# LEDs.net
KiCad netlist of a schematic drawn in Altium Designer
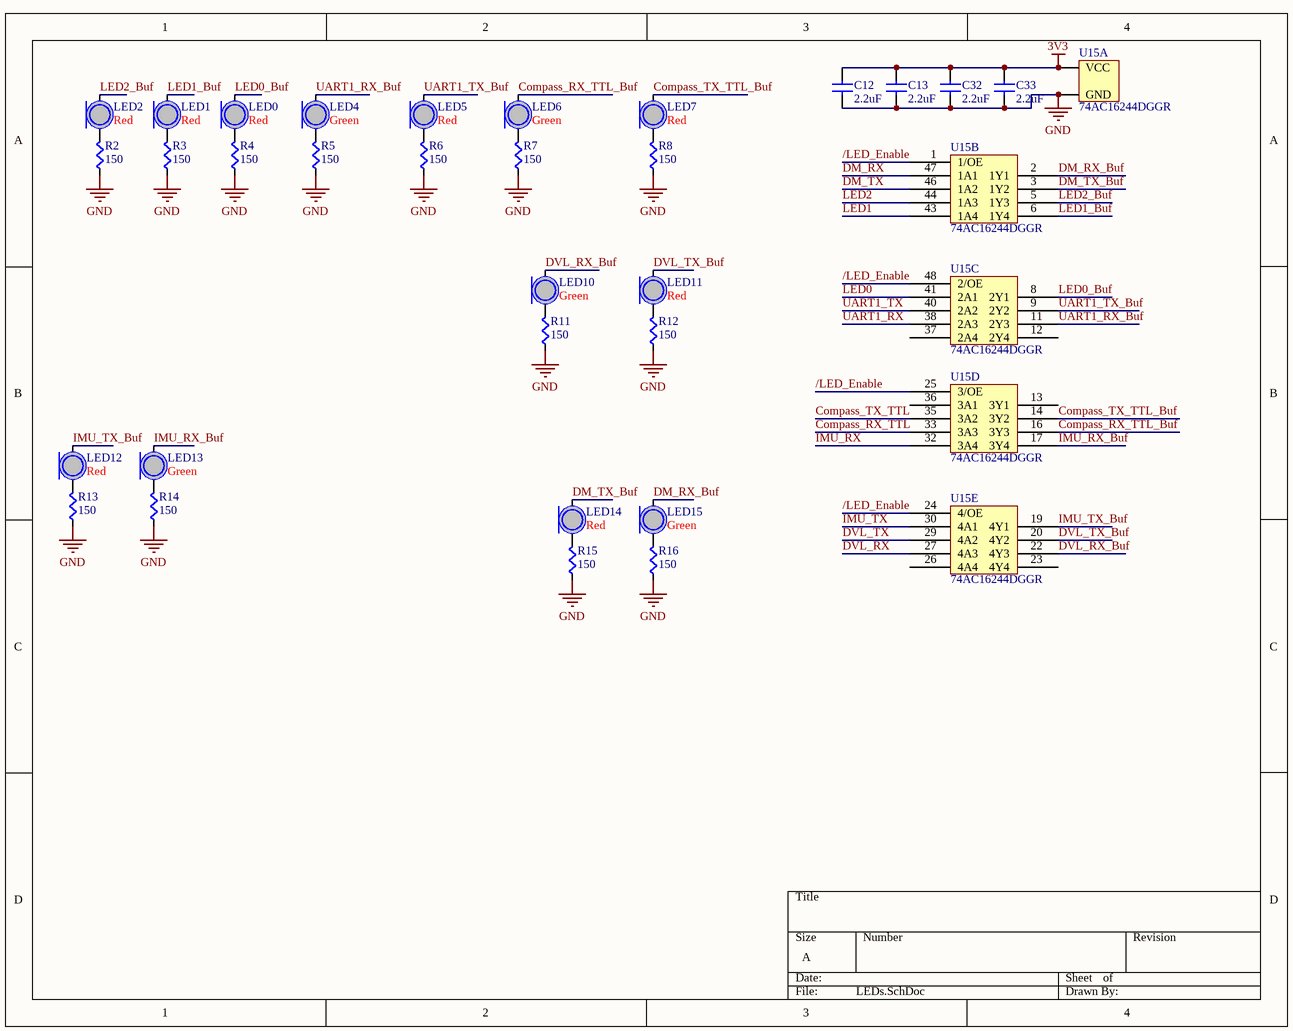
[diagram p0: LEDs.SchDoc]

(export (version "E")
  (design (tool "Eeschema 10.0.6"))
  (components
    (comp (ref "C12")
      (value "2.2uF")
      (footprint "CAPC0603")
      (fields (field (name "Comment") "Cap"))
      (libsource (lib "SubjuGator8") (part "Cap"))
    )
    (comp (ref "C13")
      (value "2.2uF")
      (footprint "CAPC0603")
      (fields (field (name "Comment") "Cap"))
      (libsource (lib "SubjuGator8") (part "Cap"))
    )
    (comp (ref "C32")
      (value "2.2uF")
      (footprint "CAPC0603")
      (fields (field (name "Comment") "Cap"))
      (libsource (lib "SubjuGator8") (part "Cap"))
    )
    (comp (ref "C33")
      (value "2.2uF")
      (footprint "CAPC0603")
      (fields (field (name "Comment") "Cap"))
      (libsource (lib "SubjuGator8") (part "Cap"))
    )
    (comp (ref "LED0")
      (value "LED")
      (footprint "LED0603")
      (fields (field (name "COLOR") "Red"))
      (libsource (lib "SubjuGator8") (part "LED"))
    )
    (comp (ref "LED1")
      (value "LED")
      (footprint "LED0603")
      (fields (field (name "COLOR") "Red"))
      (libsource (lib "SubjuGator8") (part "LED"))
    )
    (comp (ref "LED2")
      (value "LED")
      (footprint "LED0603")
      (fields (field (name "COLOR") "Red"))
      (libsource (lib "SubjuGator8") (part "LED"))
    )
    (comp (ref "LED4")
      (value "LED")
      (footprint "LED0603")
      (fields (field (name "COLOR") "Green"))
      (libsource (lib "SubjuGator8") (part "LED"))
    )
    (comp (ref "LED5")
      (value "LED")
      (footprint "LED0603")
      (fields (field (name "COLOR") "Red"))
      (libsource (lib "SubjuGator8") (part "LED"))
    )
    (comp (ref "LED6")
      (value "LED")
      (footprint "LED0603")
      (fields (field (name "COLOR") "Green"))
      (libsource (lib "SubjuGator8") (part "LED"))
    )
    (comp (ref "LED7")
      (value "LED")
      (footprint "LED0603")
      (fields (field (name "COLOR") "Red"))
      (libsource (lib "SubjuGator8") (part "LED"))
    )
    (comp (ref "LED10")
      (value "LED")
      (footprint "LED0603")
      (fields (field (name "COLOR") "Green"))
      (libsource (lib "SubjuGator8") (part "LED"))
    )
    (comp (ref "LED11")
      (value "LED")
      (footprint "LED0603")
      (fields (field (name "COLOR") "Red"))
      (libsource (lib "SubjuGator8") (part "LED"))
    )
    (comp (ref "LED12")
      (value "LED")
      (footprint "LED0603")
      (fields (field (name "COLOR") "Red"))
      (libsource (lib "SubjuGator8") (part "LED"))
    )
    (comp (ref "LED13")
      (value "LED")
      (footprint "LED0603")
      (fields (field (name "COLOR") "Green"))
      (libsource (lib "SubjuGator8") (part "LED"))
    )
    (comp (ref "LED14")
      (value "LED")
      (footprint "LED0603")
      (fields (field (name "COLOR") "Red"))
      (libsource (lib "SubjuGator8") (part "LED"))
    )
    (comp (ref "LED15")
      (value "LED")
      (footprint "LED0603")
      (fields (field (name "COLOR") "Green"))
      (libsource (lib "SubjuGator8") (part "LED"))
    )
    (comp (ref "R2")
      (value "150")
      (footprint "RES0603")
      (fields (field (name "Comment") "Res"))
      (libsource (lib "SubjuGator8") (part "Res"))
    )
    (comp (ref "R3")
      (value "150")
      (footprint "RES0603")
      (fields (field (name "Comment") "Res"))
      (libsource (lib "SubjuGator8") (part "Res"))
    )
    (comp (ref "R4")
      (value "150")
      (footprint "RES0603")
      (fields (field (name "Comment") "Res"))
      (libsource (lib "SubjuGator8") (part "Res"))
    )
    (comp (ref "R5")
      (value "150")
      (footprint "RES0603")
      (fields (field (name "Comment") "Res"))
      (libsource (lib "SubjuGator8") (part "Res"))
    )
    (comp (ref "R6")
      (value "150")
      (footprint "RES0603")
      (fields (field (name "Comment") "Res"))
      (libsource (lib "SubjuGator8") (part "Res"))
    )
    (comp (ref "R7")
      (value "150")
      (footprint "RES0603")
      (fields (field (name "Comment") "Res"))
      (libsource (lib "SubjuGator8") (part "Res"))
    )
    (comp (ref "R8")
      (value "150")
      (footprint "RES0603")
      (fields (field (name "Comment") "Res"))
      (libsource (lib "SubjuGator8") (part "Res"))
    )
    (comp (ref "R11")
      (value "150")
      (footprint "RES0603")
      (fields (field (name "Comment") "Res"))
      (libsource (lib "SubjuGator8") (part "Res"))
    )
    (comp (ref "R12")
      (value "150")
      (footprint "RES0603")
      (fields (field (name "Comment") "Res"))
      (libsource (lib "SubjuGator8") (part "Res"))
    )
    (comp (ref "R13")
      (value "150")
      (footprint "RES0603")
      (fields (field (name "Comment") "Res"))
      (libsource (lib "SubjuGator8") (part "Res"))
    )
    (comp (ref "R14")
      (value "150")
      (footprint "RES0603")
      (fields (field (name "Comment") "Res"))
      (libsource (lib "SubjuGator8") (part "Res"))
    )
    (comp (ref "R15")
      (value "150")
      (footprint "RES0603")
      (fields (field (name "Comment") "Res"))
      (libsource (lib "SubjuGator8") (part "Res"))
    )
    (comp (ref "R16")
      (value "150")
      (footprint "RES0603")
      (fields (field (name "Comment") "Res"))
      (libsource (lib "SubjuGator8") (part "Res"))
    )
    (comp (ref "U15")
      (value "74AC16244DGGR")
      (footprint "74AC16244DGGR")
      (description "IC BUFF/DVR TRI-ST 16BIT 48TSSOP")
      (libsource (lib "SubjuGator8") (part "74AC16244DGGR"))
    )
  )
  (nets
    (net (code "1") (name "/Compass_RX_TTL") (class "Default")
      (node (ref "U15") (pin "33") (pinfunction "3A3_33") (pintype "passive"))
    )
    (net (code "2") (name "/Compass_RX_TTL_Buf") (class "Default")
      (node (ref "LED6") (pin "A") (pinfunction "A_A") (pintype "passive"))
      (node (ref "U15") (pin "16") (pinfunction "3Y3_16") (pintype "passive"))
    )
    (net (code "3") (name "/Compass_TX_TTL") (class "Default")
      (node (ref "U15") (pin "35") (pinfunction "3A2_35") (pintype "passive"))
    )
    (net (code "4") (name "/Compass_TX_TTL_Buf") (class "Default")
      (node (ref "LED7") (pin "A") (pinfunction "A_A") (pintype "passive"))
      (node (ref "U15") (pin "14") (pinfunction "3Y2_14") (pintype "passive"))
    )
    (net (code "5") (name "/DM_RX") (class "Default")
      (node (ref "U15") (pin "47") (pinfunction "1A1_47") (pintype "passive"))
    )
    (net (code "6") (name "/DM_RX_Buf") (class "Default")
      (node (ref "LED15") (pin "A") (pinfunction "A_A") (pintype "passive"))
      (node (ref "U15") (pin "2") (pinfunction "1Y1_2") (pintype "passive"))
    )
    (net (code "7") (name "/DM_TX") (class "Default")
      (node (ref "U15") (pin "46") (pinfunction "1A2_46") (pintype "passive"))
    )
    (net (code "8") (name "/DM_TX_Buf") (class "Default")
      (node (ref "LED14") (pin "A") (pinfunction "A_A") (pintype "passive"))
      (node (ref "U15") (pin "3") (pinfunction "1Y2_3") (pintype "passive"))
    )
    (net (code "9") (name "/DVL_RX") (class "Default")
      (node (ref "U15") (pin "27") (pinfunction "4A3_27") (pintype "passive"))
    )
    (net (code "10") (name "/DVL_RX_Buf") (class "Default")
      (node (ref "LED10") (pin "A") (pinfunction "A_A") (pintype "passive"))
      (node (ref "U15") (pin "22") (pinfunction "4Y3_22") (pintype "passive"))
    )
    (net (code "11") (name "/DVL_TX") (class "Default")
      (node (ref "U15") (pin "29") (pinfunction "4A2_29") (pintype "passive"))
    )
    (net (code "12") (name "/DVL_TX_Buf") (class "Default")
      (node (ref "LED11") (pin "A") (pinfunction "A_A") (pintype "passive"))
      (node (ref "U15") (pin "20") (pinfunction "4Y2_20") (pintype "passive"))
    )
    (net (code "13") (name "/IMU_RX") (class "Default")
      (node (ref "U15") (pin "32") (pinfunction "3A4_32") (pintype "passive"))
    )
    (net (code "14") (name "/IMU_RX_Buf") (class "Default")
      (node (ref "LED13") (pin "A") (pinfunction "A_A") (pintype "passive"))
      (node (ref "U15") (pin "17") (pinfunction "3Y4_17") (pintype "passive"))
    )
    (net (code "15") (name "/IMU_TX") (class "Default")
      (node (ref "U15") (pin "30") (pinfunction "4A1_30") (pintype "passive"))
    )
    (net (code "16") (name "/IMU_TX_Buf") (class "Default")
      (node (ref "LED12") (pin "A") (pinfunction "A_A") (pintype "passive"))
      (node (ref "U15") (pin "19") (pinfunction "4Y1_19") (pintype "passive"))
    )
    (net (code "17") (name "/LED0") (class "Default")
      (node (ref "U15") (pin "41") (pinfunction "2A1_41") (pintype "passive"))
    )
    (net (code "18") (name "/LED0_Buf") (class "Default")
      (node (ref "LED0") (pin "A") (pinfunction "A_A") (pintype "passive"))
      (node (ref "U15") (pin "8") (pinfunction "2Y1_8") (pintype "passive"))
    )
    (net (code "19") (name "/LED1") (class "Default")
      (node (ref "U15") (pin "43") (pinfunction "1A4_43") (pintype "passive"))
    )
    (net (code "20") (name "/LED1_Buf") (class "Default")
      (node (ref "LED1") (pin "A") (pinfunction "A_A") (pintype "passive"))
      (node (ref "U15") (pin "6") (pinfunction "1Y4_6") (pintype "passive"))
    )
    (net (code "21") (name "/LED2") (class "Default")
      (node (ref "U15") (pin "44") (pinfunction "1A3_44") (pintype "passive"))
    )
    (net (code "22") (name "/LED2_Buf") (class "Default")
      (node (ref "LED2") (pin "A") (pinfunction "A_A") (pintype "passive"))
      (node (ref "U15") (pin "5") (pinfunction "1Y3_5") (pintype "passive"))
    )
    (net (code "23") (name "/UART1_RX") (class "Default")
      (node (ref "U15") (pin "38") (pinfunction "2A3_38") (pintype "passive"))
    )
    (net (code "24") (name "/UART1_RX_Buf") (class "Default")
      (node (ref "LED4") (pin "A") (pinfunction "A_A") (pintype "passive"))
      (node (ref "U15") (pin "11") (pinfunction "2Y3_11") (pintype "passive"))
    )
    (net (code "25") (name "/UART1_TX") (class "Default")
      (node (ref "U15") (pin "40") (pinfunction "2A2_40") (pintype "passive"))
    )
    (net (code "26") (name "/UART1_TX_Buf") (class "Default")
      (node (ref "LED5") (pin "A") (pinfunction "A_A") (pintype "passive"))
      (node (ref "U15") (pin "9") (pinfunction "2Y2_9") (pintype "passive"))
    )
    (net (code "27") (name "/{slash}LED_Enable") (class "Default")
      (node (ref "U15") (pin "1") (pinfunction "1/OE_1") (pintype "passive"))
      (node (ref "U15") (pin "24") (pinfunction "4/OE_24") (pintype "passive"))
      (node (ref "U15") (pin "25") (pinfunction "3/OE_25") (pintype "passive"))
      (node (ref "U15") (pin "48") (pinfunction "2/OE_48") (pintype "passive"))
    )
    (net (code "28") (name "3V3") (class "Default")
      (node (ref "C12") (pin "1") (pinfunction "A_1") (pintype "passive"))
      (node (ref "C13") (pin "1") (pinfunction "A_1") (pintype "passive"))
      (node (ref "C32") (pin "1") (pinfunction "A_1") (pintype "passive"))
      (node (ref "C33") (pin "1") (pinfunction "A_1") (pintype "passive"))
      (node (ref "U15") (pin "VCC") (pinfunction "VCC_VCC") (pintype "passive"))
    )
    (net (code "29") (name "GND") (class "Default")
      (node (ref "C12") (pin "2") (pinfunction "B_2") (pintype "passive"))
      (node (ref "C13") (pin "2") (pinfunction "B_2") (pintype "passive"))
      (node (ref "C32") (pin "2") (pinfunction "B_2") (pintype "passive"))
      (node (ref "C33") (pin "2") (pinfunction "B_2") (pintype "passive"))
      (node (ref "R11") (pin "2") (pinfunction "B_2") (pintype "passive"))
      (node (ref "R12") (pin "2") (pinfunction "B_2") (pintype "passive"))
      (node (ref "R13") (pin "2") (pinfunction "B_2") (pintype "passive"))
      (node (ref "R14") (pin "2") (pinfunction "B_2") (pintype "passive"))
      (node (ref "R15") (pin "2") (pinfunction "B_2") (pintype "passive"))
      (node (ref "R16") (pin "2") (pinfunction "B_2") (pintype "passive"))
      (node (ref "R2") (pin "2") (pinfunction "B_2") (pintype "passive"))
      (node (ref "R3") (pin "2") (pinfunction "B_2") (pintype "passive"))
      (node (ref "R4") (pin "2") (pinfunction "B_2") (pintype "passive"))
      (node (ref "R5") (pin "2") (pinfunction "B_2") (pintype "passive"))
      (node (ref "R6") (pin "2") (pinfunction "B_2") (pintype "passive"))
      (node (ref "R7") (pin "2") (pinfunction "B_2") (pintype "passive"))
      (node (ref "R8") (pin "2") (pinfunction "B_2") (pintype "passive"))
      (node (ref "U15") (pin "GND") (pinfunction "GND_GND") (pintype "passive"))
    )
    (net (code "30") (name "Net-(R2-A)") (class "Default")
      (node (ref "LED2") (pin "C") (pinfunction "C_C") (pintype "passive"))
      (node (ref "R2") (pin "1") (pinfunction "A_1") (pintype "passive"))
    )
    (net (code "31") (name "Net-(R3-A)") (class "Default")
      (node (ref "LED1") (pin "C") (pinfunction "C_C") (pintype "passive"))
      (node (ref "R3") (pin "1") (pinfunction "A_1") (pintype "passive"))
    )
    (net (code "32") (name "Net-(R4-A)") (class "Default")
      (node (ref "LED0") (pin "C") (pinfunction "C_C") (pintype "passive"))
      (node (ref "R4") (pin "1") (pinfunction "A_1") (pintype "passive"))
    )
    (net (code "33") (name "Net-(R5-A)") (class "Default")
      (node (ref "LED4") (pin "C") (pinfunction "C_C") (pintype "passive"))
      (node (ref "R5") (pin "1") (pinfunction "A_1") (pintype "passive"))
    )
    (net (code "34") (name "Net-(R6-A)") (class "Default")
      (node (ref "LED5") (pin "C") (pinfunction "C_C") (pintype "passive"))
      (node (ref "R6") (pin "1") (pinfunction "A_1") (pintype "passive"))
    )
    (net (code "35") (name "Net-(R7-A)") (class "Default")
      (node (ref "LED6") (pin "C") (pinfunction "C_C") (pintype "passive"))
      (node (ref "R7") (pin "1") (pinfunction "A_1") (pintype "passive"))
    )
    (net (code "36") (name "Net-(R8-A)") (class "Default")
      (node (ref "LED7") (pin "C") (pinfunction "C_C") (pintype "passive"))
      (node (ref "R8") (pin "1") (pinfunction "A_1") (pintype "passive"))
    )
    (net (code "37") (name "Net-(R11-A)") (class "Default")
      (node (ref "LED10") (pin "C") (pinfunction "C_C") (pintype "passive"))
      (node (ref "R11") (pin "1") (pinfunction "A_1") (pintype "passive"))
    )
    (net (code "38") (name "Net-(R12-A)") (class "Default")
      (node (ref "LED11") (pin "C") (pinfunction "C_C") (pintype "passive"))
      (node (ref "R12") (pin "1") (pinfunction "A_1") (pintype "passive"))
    )
    (net (code "39") (name "Net-(R13-A)") (class "Default")
      (node (ref "LED12") (pin "C") (pinfunction "C_C") (pintype "passive"))
      (node (ref "R13") (pin "1") (pinfunction "A_1") (pintype "passive"))
    )
    (net (code "40") (name "Net-(R14-A)") (class "Default")
      (node (ref "LED13") (pin "C") (pinfunction "C_C") (pintype "passive"))
      (node (ref "R14") (pin "1") (pinfunction "A_1") (pintype "passive"))
    )
    (net (code "41") (name "Net-(R15-A)") (class "Default")
      (node (ref "LED14") (pin "C") (pinfunction "C_C") (pintype "passive"))
      (node (ref "R15") (pin "1") (pinfunction "A_1") (pintype "passive"))
    )
    (net (code "42") (name "Net-(R16-A)") (class "Default")
      (node (ref "LED15") (pin "C") (pinfunction "C_C") (pintype "passive"))
      (node (ref "R16") (pin "1") (pinfunction "A_1") (pintype "passive"))
    )
    (net (code "43") (name "unconnected-(U15C-2A4-Pad37)") (class "Default")
      (node (ref "U15") (pin "37") (pinfunction "2A4_37") (pintype "passive"))
    )
    (net (code "44") (name "unconnected-(U15C-2Y4-Pad12)") (class "Default")
      (node (ref "U15") (pin "12") (pinfunction "2Y4_12") (pintype "passive"))
    )
    (net (code "45") (name "unconnected-(U15D-3A1-Pad36)") (class "Default")
      (node (ref "U15") (pin "36") (pinfunction "3A1_36") (pintype "passive"))
    )
    (net (code "46") (name "unconnected-(U15D-3Y1-Pad13)") (class "Default")
      (node (ref "U15") (pin "13") (pinfunction "3Y1_13") (pintype "passive"))
    )
    (net (code "47") (name "unconnected-(U15E-4A4-Pad26)") (class "Default")
      (node (ref "U15") (pin "26") (pinfunction "4A4_26") (pintype "passive"))
    )
    (net (code "48") (name "unconnected-(U15E-4Y4-Pad23)") (class "Default")
      (node (ref "U15") (pin "23") (pinfunction "4Y4_23") (pintype "passive"))
    )
  )
)
